# Microcontroller.net
KiCad netlist of a schematic drawn in Altium Designer
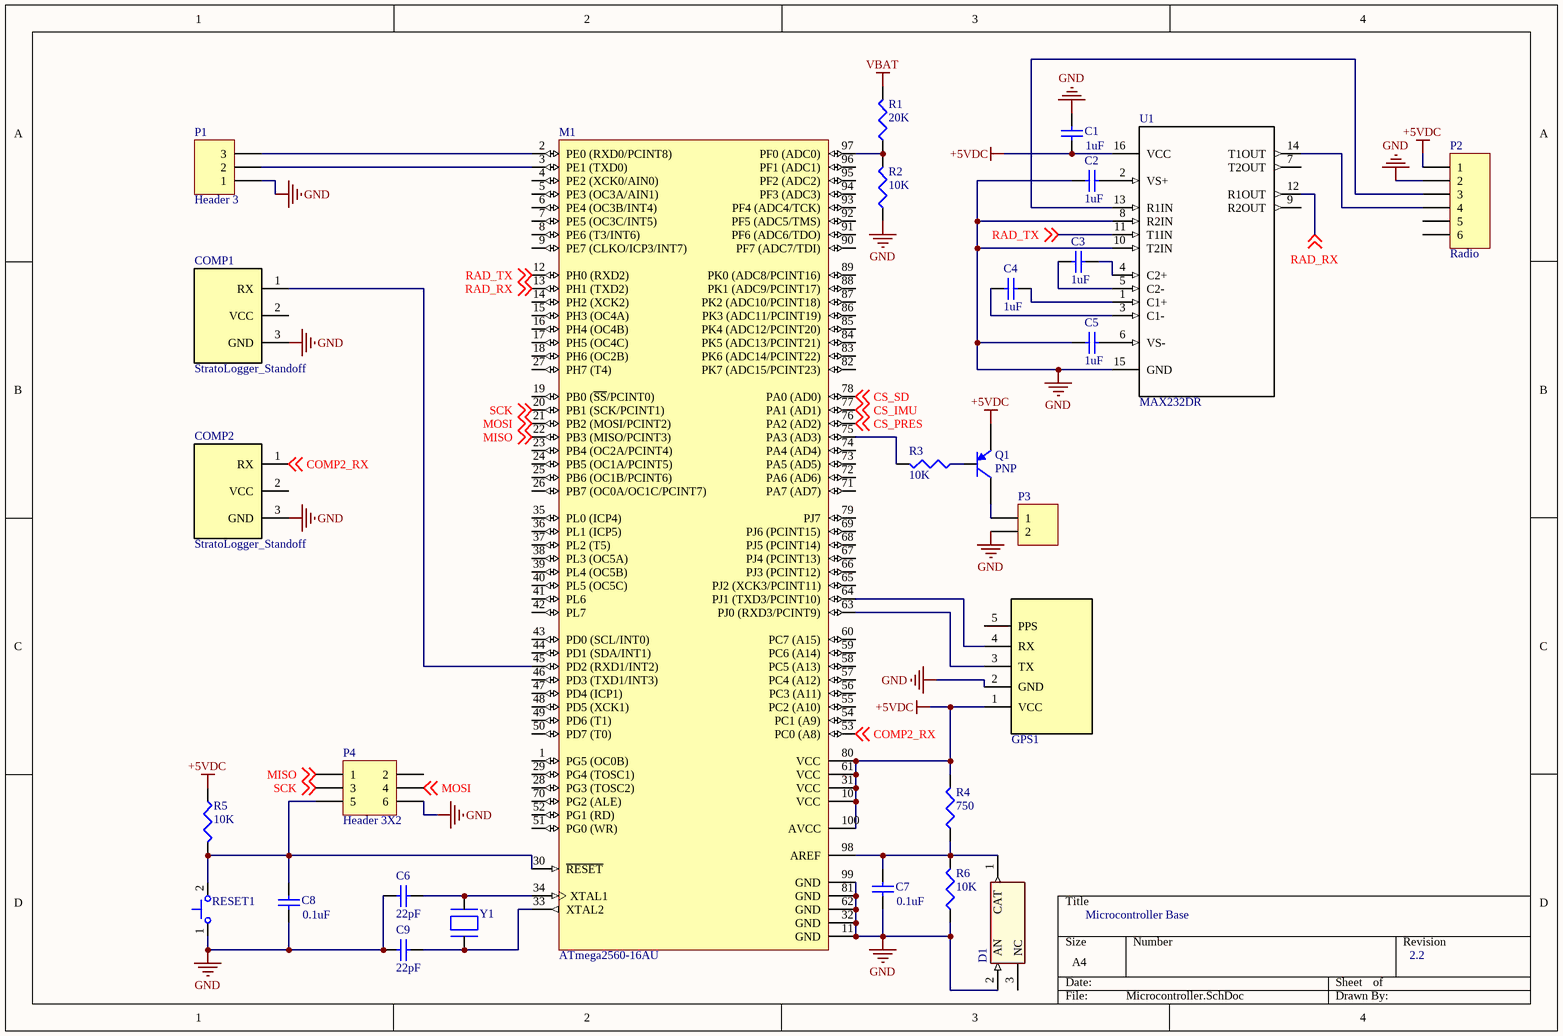
[diagram p0: Microcontroller.SchDoc]

(export (version "E")
  (design (tool "Eeschema 10.0.6"))
  (components
    (comp (ref "C1")
      (value "1uF")
      (footprint "1608[0603]")
      (description "Capacitor (Semiconductor SIM Model)")
      (fields (field (name "Comment") "Cap Semi") (field (name "PUBLISHER") "Altium Limited"))
      (libsource (lib "Miscellaneous Devices") (part "Cap Semi"))
    )
    (comp (ref "C2")
      (value "1uF")
      (footprint "1608[0603]")
      (description "Capacitor (Semiconductor SIM Model)")
      (fields (field (name "Comment") "Cap Semi") (field (name "PUBLISHER") "Altium Limited"))
      (libsource (lib "Miscellaneous Devices") (part "Cap Semi"))
    )
    (comp (ref "C3")
      (value "1uF")
      (footprint "1608[0603]")
      (description "Capacitor (Semiconductor SIM Model)")
      (fields (field (name "Comment") "Cap Semi") (field (name "PUBLISHER") "Altium Limited"))
      (libsource (lib "Miscellaneous Devices") (part "Cap Semi"))
    )
    (comp (ref "C4")
      (value "1uF")
      (footprint "1608[0603]")
      (description "Capacitor (Semiconductor SIM Model)")
      (fields (field (name "Comment") "Cap Semi") (field (name "PUBLISHER") "Altium Limited"))
      (libsource (lib "Miscellaneous Devices") (part "Cap Semi"))
    )
    (comp (ref "C5")
      (value "1uF")
      (footprint "1608[0603]")
      (description "Capacitor (Semiconductor SIM Model)")
      (fields (field (name "Comment") "Cap Semi") (field (name "PUBLISHER") "Altium Limited"))
      (libsource (lib "Miscellaneous Devices") (part "Cap Semi"))
    )
    (comp (ref "C6")
      (value "22pF")
      (footprint "1608[0603]")
      (description "Capacitor (Semiconductor SIM Model)")
      (fields (field (name "Comment") "Cap Semi") (field (name "PUBLISHER") "Altium Limited"))
      (libsource (lib "Miscellaneous Devices") (part "Cap Semi"))
    )
    (comp (ref "C7")
      (value "0.1uF")
      (footprint "1608[0603]")
      (description "Capacitor (Semiconductor SIM Model)")
      (fields (field (name "Comment") "Cap Semi") (field (name "PUBLISHER") "Altium Limited"))
      (libsource (lib "Miscellaneous Devices") (part "Cap Semi"))
    )
    (comp (ref "C8")
      (value "0.1uF")
      (footprint "1608[0603]")
      (description "Capacitor (Semiconductor SIM Model)")
      (fields (field (name "Comment") "Cap Semi") (field (name "PUBLISHER") "Altium Limited"))
      (libsource (lib "Miscellaneous Devices") (part "Cap Semi"))
    )
    (comp (ref "C9")
      (value "22pF")
      (footprint "1608[0603]")
      (description "Capacitor (Semiconductor SIM Model)")
      (fields (field (name "Comment") "Cap Semi") (field (name "PUBLISHER") "Altium Limited"))
      (libsource (lib "Miscellaneous Devices") (part "Cap Semi"))
    )
    (comp (ref "COMP1")
      (value "StratoLogger_Standoff")
      (footprint "StratoLogger_S")
      (libsource (lib "CustomCompLib") (part "StratoLogger_Standoff"))
    )
    (comp (ref "COMP2")
      (value "StratoLogger_Standoff")
      (footprint "StratoLogger_S")
      (libsource (lib "CustomCompLib") (part "StratoLogger_Standoff"))
    )
    (comp (ref "D1")
      (value "LM4040A82IDBZR")
      (footprint "SOT95P237X112-3N")
      (description "Precision Micropower Shunt Voltage Reference, 0.1% accuracy 3-SOT-23 -40 to 85")
      (fields (field (name "MF") "Texas Instruments"))
      (libsource (lib "CustomCompLib") (part "LM4040A82IDBZR"))
    )
    (comp (ref "GPS1")
      (value "Neo 6M GPS")
      (footprint "Neo 6M GPS")
      (libsource (lib "CustomCompLib") (part "Neo 6M GPS"))
    )
    (comp (ref "M1")
      (value "ATmega2560-16AU")
      (footprint "100A_N")
      (fields (field (name "PUBLISHER") "Altium Limited"))
      (libsource (lib "Atmel Microcontroller 8-Bit megaAVR") (part "ATmega2560-16AU"))
    )
    (comp (ref "P1")
      (value "Header 3")
      (footprint "HDR1X3")
      (description "Header, 3-Pin")
      (fields (field (name "PUBLISHER") "Altium Limited"))
      (libsource (lib "Miscellaneous Connectors") (part "Header 3"))
    )
    (comp (ref "P2")
      (value "Radio")
      (footprint "HDR1X6")
      (description "Header, 6-Pin")
      (fields (field (name "PUBLISHER") "Altium Limited"))
      (libsource (lib "Miscellaneous Connectors") (part "Header 6"))
    )
    (comp (ref "P3")
      (value "Header 2")
      (footprint "HDR1X2")
      (description "Header, 2-Pin")
      (fields (field (name "PUBLISHER") "Altium Limited"))
      (libsource (lib "Miscellaneous Connectors") (part "Header 2"))
    )
    (comp (ref "P4")
      (value "Header 3X2")
      (footprint "HDR2X3")
      (description "Header, 3-Pin, Dual row")
      (fields (field (name "PUBLISHER") "Altium Limited"))
      (libsource (lib "Miscellaneous Connectors") (part "Header 3X2"))
    )
    (comp (ref "Q1")
      (value "PNP")
      (footprint "SOT-23B_N")
      (description "PNP Bipolar Transistor")
      (fields (field (name "PUBLISHER") "Altium Limited"))
      (libsource (lib "Miscellaneous Devices") (part "PNP"))
    )
    (comp (ref "R1")
      (value "20K")
      (footprint "J1-0603")
      (description "Resistor")
      (fields (field (name "Comment") "Res3") (field (name "PUBLISHER") "Altium Limited"))
      (libsource (lib "Miscellaneous Devices") (part "Res3"))
    )
    (comp (ref "R2")
      (value "10K")
      (footprint "J1-0603")
      (description "Resistor")
      (fields (field (name "Comment") "Res3") (field (name "PUBLISHER") "Altium Limited"))
      (libsource (lib "Miscellaneous Devices") (part "Res3"))
    )
    (comp (ref "R3")
      (value "10K")
      (footprint "J1-0603")
      (description "Resistor")
      (fields (field (name "Comment") "Res3") (field (name "PUBLISHER") "Altium Limited"))
      (libsource (lib "Miscellaneous Devices") (part "Res3"))
    )
    (comp (ref "R4")
      (value "750")
      (footprint "J1-0603")
      (description "Resistor")
      (fields (field (name "Comment") "Res3") (field (name "PUBLISHER") "Altium Limited"))
      (libsource (lib "Miscellaneous Devices") (part "Res3"))
    )
    (comp (ref "R5")
      (value "10K")
      (footprint "J1-0603")
      (description "Resistor")
      (fields (field (name "Comment") "Res3") (field (name "PUBLISHER") "Altium Limited"))
      (libsource (lib "Miscellaneous Devices") (part "Res3"))
    )
    (comp (ref "R6")
      (value "10K")
      (footprint "J1-0603")
      (description "Resistor")
      (fields (field (name "Comment") "Res3") (field (name "PUBLISHER") "Altium Limited"))
      (libsource (lib "Miscellaneous Devices") (part "Res3"))
    )
    (comp (ref "RESET1")
      (value "KSS221GLFS")
      (footprint "KSS-2G")
      (fields (field (name "PUBLISHER") "Altium Limited"))
      (libsource (lib "CK Switch") (part "KSS221GLFS"))
    )
    (comp (ref "U1")
      (value "MAX232DR")
      (footprint "SOIC127P600X175-16N")
      (description "Single Supply Voltage, RS-232 Transceiver")
      (fields (field (name "MF") "Texas Instruments"))
      (libsource (lib "MAX232DR") (part "MAX232DR"))
    )
    (comp (ref "Y1")
      (value "Crystal SMD")
      (footprint "Crystal SMD")
      (libsource (lib "CustomCompLib") (part "Crystal SMD"))
    )
  )
  (nets
    (net (code "1") (name "+5VDC") (class "Default")
      (node (ref "C1") (pin "1") (pinfunction "1_1") (pintype "passive"))
      (node (ref "GPS1") (pin "1") (pinfunction "VCC_1") (pintype "passive"))
      (node (ref "M1") (pin "10") (pinfunction "VCC_10") (pintype "power_in"))
      (node (ref "M1") (pin "100") (pinfunction "AVCC_100") (pintype "power_in"))
      (node (ref "M1") (pin "31") (pinfunction "VCC_31") (pintype "power_in"))
      (node (ref "M1") (pin "61") (pinfunction "VCC_61") (pintype "power_in"))
      (node (ref "M1") (pin "80") (pinfunction "VCC_80") (pintype "power_in"))
      (node (ref "P2") (pin "1") (pinfunction "1_1") (pintype "passive"))
      (node (ref "Q1") (pin "3") (pinfunction "E_3") (pintype "passive"))
      (node (ref "R4") (pin "2") (pinfunction "2_2") (pintype "passive"))
      (node (ref "R5") (pin "1") (pinfunction "1_1") (pintype "passive"))
      (node (ref "U1") (pin "16") (pinfunction "VCC_16") (pintype "power_in"))
    )
    (net (code "2") (name "COMP2_RX") (class "Default")
      (node (ref "COMP2") (pin "1") (pinfunction "RX_1") (pintype "passive"))
      (node (ref "M1") (pin "53") (pinfunction "PC0_(A8)_53") (pintype "bidirectional"))
    )
    (net (code "3") (name "CS_IMU") (class "Default")
      (node (ref "M1") (pin "77") (pinfunction "PA1_(AD1)_77") (pintype "bidirectional"))
    )
    (net (code "4") (name "CS_PRES") (class "Default")
      (node (ref "M1") (pin "76") (pinfunction "PA2_(AD2)_76") (pintype "bidirectional"))
    )
    (net (code "5") (name "CS_SD") (class "Default")
      (node (ref "M1") (pin "78") (pinfunction "PA0_(AD0)_78") (pintype "bidirectional"))
    )
    (net (code "6") (name "GND") (class "Default")
      (node (ref "C1") (pin "2") (pinfunction "2_2") (pintype "passive"))
      (node (ref "C2") (pin "2") (pinfunction "2_2") (pintype "passive"))
      (node (ref "C5") (pin "2") (pinfunction "2_2") (pintype "passive"))
      (node (ref "C6") (pin "1") (pinfunction "1_1") (pintype "passive"))
      (node (ref "C7") (pin "1") (pinfunction "1_1") (pintype "passive"))
      (node (ref "C8") (pin "1") (pinfunction "1_1") (pintype "passive"))
      (node (ref "C9") (pin "1") (pinfunction "1_1") (pintype "passive"))
      (node (ref "COMP1") (pin "3") (pinfunction "GND_3") (pintype "passive"))
      (node (ref "COMP2") (pin "3") (pinfunction "GND_3") (pintype "passive"))
      (node (ref "D1") (pin "2") (pinfunction "AN_2") (pintype "input"))
      (node (ref "GPS1") (pin "2") (pinfunction "GND_2") (pintype "passive"))
      (node (ref "M1") (pin "11") (pinfunction "GND_11") (pintype "power_in"))
      (node (ref "M1") (pin "32") (pinfunction "GND_32") (pintype "power_in"))
      (node (ref "M1") (pin "62") (pinfunction "GND_62") (pintype "power_in"))
      (node (ref "M1") (pin "81") (pinfunction "GND_81") (pintype "power_in"))
      (node (ref "M1") (pin "99") (pinfunction "GND_99") (pintype "power_in"))
      (node (ref "P1") (pin "1") (pinfunction "1_1") (pintype "passive"))
      (node (ref "P2") (pin "2") (pinfunction "2_2") (pintype "passive"))
      (node (ref "P3") (pin "2") (pinfunction "2_2") (pintype "passive"))
      (node (ref "P4") (pin "6") (pinfunction "6_6") (pintype "passive"))
      (node (ref "R2") (pin "1") (pinfunction "1_1") (pintype "passive"))
      (node (ref "R6") (pin "1") (pinfunction "1_1") (pintype "passive"))
      (node (ref "RESET1") (pin "1") (pinfunction "1_1") (pintype "passive"))
      (node (ref "U1") (pin "10") (pinfunction "T2IN_10") (pintype "input"))
      (node (ref "U1") (pin "15") (pinfunction "GND_15") (pintype "passive"))
      (node (ref "U1") (pin "8") (pinfunction "R2IN_8") (pintype "input"))
    )
    (net (code "7") (name "MISO") (class "Default")
      (node (ref "M1") (pin "22") (pinfunction "PB3_(MISO/PCINT3)_22") (pintype "bidirectional"))
      (node (ref "P4") (pin "1") (pinfunction "1_1") (pintype "passive"))
    )
    (net (code "8") (name "MOSI") (class "Default")
      (node (ref "M1") (pin "21") (pinfunction "PB2_(MOSI/PCINT2)_21") (pintype "bidirectional"))
      (node (ref "P4") (pin "4") (pinfunction "4_4") (pintype "passive"))
    )
    (net (code "9") (name "Net-(COMP1-RX)") (class "Default")
      (node (ref "COMP1") (pin "1") (pinfunction "RX_1") (pintype "passive"))
      (node (ref "M1") (pin "45") (pinfunction "PD2_(RXD1/INT2)_45") (pintype "bidirectional"))
    )
    (net (code "10") (name "Net-(D1-CAT)") (class "Default")
      (node (ref "C7") (pin "2") (pinfunction "2_2") (pintype "passive"))
      (node (ref "D1") (pin "1") (pinfunction "CAT_1") (pintype "output"))
      (node (ref "M1") (pin "98") (pinfunction "AREF_98") (pintype "power_in"))
      (node (ref "R4") (pin "1") (pinfunction "1_1") (pintype "passive"))
      (node (ref "R6") (pin "2") (pinfunction "2_2") (pintype "passive"))
    )
    (net (code "11") (name "Net-(GPS1-RX)") (class "Default")
      (node (ref "GPS1") (pin "4") (pinfunction "RX_4") (pintype "passive"))
      (node (ref "M1") (pin "64") (pinfunction "PJ1_(TXD3/PCINT10)_64") (pintype "bidirectional"))
    )
    (net (code "12") (name "Net-(GPS1-TX)") (class "Default")
      (node (ref "GPS1") (pin "3") (pinfunction "TX_3") (pintype "passive"))
      (node (ref "M1") (pin "63") (pinfunction "PJ0_(RXD3/PCINT9)_63") (pintype "bidirectional"))
    )
    (net (code "13") (name "Net-(M1-PA3_(AD3))") (class "Default")
      (node (ref "M1") (pin "75") (pinfunction "PA3_(AD3)_75") (pintype "bidirectional"))
      (node (ref "R3") (pin "2") (pinfunction "2_2") (pintype "passive"))
    )
    (net (code "14") (name "Net-(M1-PE0_(RXD0{slash}PCINT8))") (class "Default")
      (node (ref "M1") (pin "2") (pinfunction "PE0_(RXD0/PCINT8)_2") (pintype "bidirectional"))
      (node (ref "P1") (pin "3") (pinfunction "3_3") (pintype "passive"))
    )
    (net (code "15") (name "Net-(M1-PE1_(TXD0))") (class "Default")
      (node (ref "M1") (pin "3") (pinfunction "PE1_(TXD0)_3") (pintype "bidirectional"))
      (node (ref "P1") (pin "2") (pinfunction "2_2") (pintype "passive"))
    )
    (net (code "16") (name "Net-(M1-PF0_(ADC0))") (class "Default")
      (node (ref "M1") (pin "97") (pinfunction "PF0_(ADC0)_97") (pintype "bidirectional"))
      (node (ref "R1") (pin "1") (pinfunction "1_1") (pintype "passive"))
      (node (ref "R2") (pin "2") (pinfunction "2_2") (pintype "passive"))
    )
    (net (code "17") (name "Net-(M1-XTAL1)") (class "Default")
      (node (ref "C6") (pin "2") (pinfunction "2_2") (pintype "passive"))
      (node (ref "M1") (pin "34") (pinfunction "XTAL1_34") (pintype "input"))
      (node (ref "Y1") (pin "1") (pinfunction "1_1") (pintype "passive"))
    )
    (net (code "18") (name "Net-(M1-XTAL2)") (class "Default")
      (node (ref "C9") (pin "2") (pinfunction "2_2") (pintype "passive"))
      (node (ref "M1") (pin "33") (pinfunction "XTAL2_33") (pintype "output"))
      (node (ref "Y1") (pin "2") (pinfunction "2_2") (pintype "passive"))
    )
    (net (code "19") (name "Net-(M1-~{RESET})") (class "Default")
      (node (ref "C8") (pin "2") (pinfunction "2_2") (pintype "passive"))
      (node (ref "M1") (pin "30") (pinfunction "~{RESET}_30") (pintype "input"))
      (node (ref "P4") (pin "5") (pinfunction "5_5") (pintype "passive"))
      (node (ref "R5") (pin "2") (pinfunction "2_2") (pintype "passive"))
      (node (ref "RESET1") (pin "2") (pinfunction "2_2") (pintype "passive"))
    )
    (net (code "20") (name "Net-(Q1-B)") (class "Default")
      (node (ref "Q1") (pin "2") (pinfunction "B_2") (pintype "passive"))
      (node (ref "R3") (pin "1") (pinfunction "1_1") (pintype "passive"))
    )
    (net (code "21") (name "Net-(Q1-C)") (class "Default")
      (node (ref "P3") (pin "1") (pinfunction "1_1") (pintype "passive"))
      (node (ref "Q1") (pin "1") (pinfunction "C_1") (pintype "passive"))
    )
    (net (code "22") (name "Net-(U1-C1+)") (class "Default")
      (node (ref "C4") (pin "1") (pinfunction "1_1") (pintype "passive"))
      (node (ref "U1") (pin "1") (pinfunction "C1+_1") (pintype "input"))
    )
    (net (code "23") (name "Net-(U1-C1-)") (class "Default")
      (node (ref "C4") (pin "2") (pinfunction "2_2") (pintype "passive"))
      (node (ref "U1") (pin "3") (pinfunction "C1-_3") (pintype "input"))
    )
    (net (code "24") (name "Net-(U1-C2+)") (class "Default")
      (node (ref "C3") (pin "1") (pinfunction "1_1") (pintype "passive"))
      (node (ref "U1") (pin "4") (pinfunction "C2+_4") (pintype "input"))
    )
    (net (code "25") (name "Net-(U1-C2-)") (class "Default")
      (node (ref "C3") (pin "2") (pinfunction "2_2") (pintype "passive"))
      (node (ref "U1") (pin "5") (pinfunction "C2-_5") (pintype "input"))
    )
    (net (code "26") (name "Net-(U1-R1IN)") (class "Default")
      (node (ref "P2") (pin "3") (pinfunction "3_3") (pintype "passive"))
      (node (ref "U1") (pin "13") (pinfunction "R1IN_13") (pintype "input"))
    )
    (net (code "27") (name "Net-(U1-T1OUT)") (class "Default")
      (node (ref "P2") (pin "4") (pinfunction "4_4") (pintype "passive"))
      (node (ref "U1") (pin "14") (pinfunction "T1OUT_14") (pintype "output"))
    )
    (net (code "28") (name "Net-(U1-VS+)") (class "Default")
      (node (ref "C2") (pin "1") (pinfunction "1_1") (pintype "passive"))
      (node (ref "U1") (pin "2") (pinfunction "VS+_2") (pintype "input"))
    )
    (net (code "29") (name "Net-(U1-VS-)") (class "Default")
      (node (ref "C5") (pin "1") (pinfunction "1_1") (pintype "passive"))
      (node (ref "U1") (pin "6") (pinfunction "VS-_6") (pintype "input"))
    )
    (net (code "30") (name "RAD_RX") (class "Default")
      (node (ref "M1") (pin "13") (pinfunction "PH1_(TXD2)_13") (pintype "bidirectional"))
      (node (ref "U1") (pin "12") (pinfunction "R1OUT_12") (pintype "output"))
    )
    (net (code "31") (name "RAD_TX") (class "Default")
      (node (ref "M1") (pin "12") (pinfunction "PH0_(RXD2)_12") (pintype "bidirectional"))
      (node (ref "U1") (pin "11") (pinfunction "T1IN_11") (pintype "input"))
    )
    (net (code "32") (name "SCK") (class "Default")
      (node (ref "M1") (pin "20") (pinfunction "PB1_(SCK/PCINT1)_20") (pintype "bidirectional"))
      (node (ref "P4") (pin "3") (pinfunction "3_3") (pintype "passive"))
    )
    (net (code "33") (name "VBAT") (class "Default")
      (node (ref "R1") (pin "2") (pinfunction "2_2") (pintype "passive"))
    )
    (net (code "34") (name "unconnected-(COMP1-VCC-Pad2)") (class "Default")
      (node (ref "COMP1") (pin "2") (pinfunction "VCC_2") (pintype "passive"))
    )
    (net (code "35") (name "unconnected-(COMP2-VCC-Pad2)") (class "Default")
      (node (ref "COMP2") (pin "2") (pinfunction "VCC_2") (pintype "passive"))
    )
    (net (code "36") (name "unconnected-(D1-NC-Pad3)") (class "Default")
      (node (ref "D1") (pin "3") (pinfunction "NC_3") (pintype "passive"))
    )
    (net (code "37") (name "unconnected-(GPS1-PPS-Pad5)") (class "Default")
      (node (ref "GPS1") (pin "5") (pinfunction "PPS_5") (pintype "passive"))
    )
    (net (code "38") (name "unconnected-(M1-PA4_(AD4)-Pad74)") (class "Default")
      (node (ref "M1") (pin "74") (pinfunction "PA4_(AD4)_74") (pintype "bidirectional"))
    )
    (net (code "39") (name "unconnected-(M1-PA5_(AD5)-Pad73)") (class "Default")
      (node (ref "M1") (pin "73") (pinfunction "PA5_(AD5)_73") (pintype "bidirectional"))
    )
    (net (code "40") (name "unconnected-(M1-PA6_(AD6)-Pad72)") (class "Default")
      (node (ref "M1") (pin "72") (pinfunction "PA6_(AD6)_72") (pintype "bidirectional"))
    )
    (net (code "41") (name "unconnected-(M1-PA7_(AD7)-Pad71)") (class "Default")
      (node (ref "M1") (pin "71") (pinfunction "PA7_(AD7)_71") (pintype "bidirectional"))
    )
    (net (code "42") (name "unconnected-(M1-PB0_(~{SS}{slash}PCINT0)-Pad19)") (class "Default")
      (node (ref "M1") (pin "19") (pinfunction "PB0_(~{SS}/PCINT0)_19") (pintype "bidirectional"))
    )
    (net (code "43") (name "unconnected-(M1-PB4_(OC2A{slash}PCINT4)-Pad23)") (class "Default")
      (node (ref "M1") (pin "23") (pinfunction "PB4_(OC2A/PCINT4)_23") (pintype "bidirectional"))
    )
    (net (code "44") (name "unconnected-(M1-PB5_(OC1A{slash}PCINT5)-Pad24)") (class "Default")
      (node (ref "M1") (pin "24") (pinfunction "PB5_(OC1A/PCINT5)_24") (pintype "bidirectional"))
    )
    (net (code "45") (name "unconnected-(M1-PB6_(OC1B{slash}PCINT6)-Pad25)") (class "Default")
      (node (ref "M1") (pin "25") (pinfunction "PB6_(OC1B/PCINT6)_25") (pintype "bidirectional"))
    )
    (net (code "46") (name "unconnected-(M1-PB7_(OC0A{slash}OC1C{slash}PCINT7)-Pad26)") (class "Default")
      (node (ref "M1") (pin "26") (pinfunction "PB7_(OC0A/OC1C/PCINT7)_26") (pintype "bidirectional"))
    )
    (net (code "47") (name "unconnected-(M1-PC1_(A9)-Pad54)") (class "Default")
      (node (ref "M1") (pin "54") (pinfunction "PC1_(A9)_54") (pintype "bidirectional"))
    )
    (net (code "48") (name "unconnected-(M1-PC2_(A10)-Pad55)") (class "Default")
      (node (ref "M1") (pin "55") (pinfunction "PC2_(A10)_55") (pintype "bidirectional"))
    )
    (net (code "49") (name "unconnected-(M1-PC3_(A11)-Pad56)") (class "Default")
      (node (ref "M1") (pin "56") (pinfunction "PC3_(A11)_56") (pintype "bidirectional"))
    )
    (net (code "50") (name "unconnected-(M1-PC4_(A12)-Pad57)") (class "Default")
      (node (ref "M1") (pin "57") (pinfunction "PC4_(A12)_57") (pintype "bidirectional"))
    )
    (net (code "51") (name "unconnected-(M1-PC5_(A13)-Pad58)") (class "Default")
      (node (ref "M1") (pin "58") (pinfunction "PC5_(A13)_58") (pintype "bidirectional"))
    )
    (net (code "52") (name "unconnected-(M1-PC6_(A14)-Pad59)") (class "Default")
      (node (ref "M1") (pin "59") (pinfunction "PC6_(A14)_59") (pintype "bidirectional"))
    )
    (net (code "53") (name "unconnected-(M1-PC7_(A15)-Pad60)") (class "Default")
      (node (ref "M1") (pin "60") (pinfunction "PC7_(A15)_60") (pintype "bidirectional"))
    )
    (net (code "54") (name "unconnected-(M1-PD0_(SCL{slash}INT0)-Pad43)") (class "Default")
      (node (ref "M1") (pin "43") (pinfunction "PD0_(SCL/INT0)_43") (pintype "bidirectional"))
    )
    (net (code "55") (name "unconnected-(M1-PD1_(SDA{slash}INT1)-Pad44)") (class "Default")
      (node (ref "M1") (pin "44") (pinfunction "PD1_(SDA/INT1)_44") (pintype "bidirectional"))
    )
    (net (code "56") (name "unconnected-(M1-PD3_(TXD1{slash}INT3)-Pad46)") (class "Default")
      (node (ref "M1") (pin "46") (pinfunction "PD3_(TXD1/INT3)_46") (pintype "bidirectional"))
    )
    (net (code "57") (name "unconnected-(M1-PD4_(ICP1)-Pad47)") (class "Default")
      (node (ref "M1") (pin "47") (pinfunction "PD4_(ICP1)_47") (pintype "bidirectional"))
    )
    (net (code "58") (name "unconnected-(M1-PD5_(XCK1)-Pad48)") (class "Default")
      (node (ref "M1") (pin "48") (pinfunction "PD5_(XCK1)_48") (pintype "bidirectional"))
    )
    (net (code "59") (name "unconnected-(M1-PD6_(T1)-Pad49)") (class "Default")
      (node (ref "M1") (pin "49") (pinfunction "PD6_(T1)_49") (pintype "bidirectional"))
    )
    (net (code "60") (name "unconnected-(M1-PD7_(T0)-Pad50)") (class "Default")
      (node (ref "M1") (pin "50") (pinfunction "PD7_(T0)_50") (pintype "bidirectional"))
    )
    (net (code "61") (name "unconnected-(M1-PE2_(XCK0{slash}AIN0)-Pad4)") (class "Default")
      (node (ref "M1") (pin "4") (pinfunction "PE2_(XCK0/AIN0)_4") (pintype "bidirectional"))
    )
    (net (code "62") (name "unconnected-(M1-PE3_(OC3A{slash}AIN1)-Pad5)") (class "Default")
      (node (ref "M1") (pin "5") (pinfunction "PE3_(OC3A/AIN1)_5") (pintype "bidirectional"))
    )
    (net (code "63") (name "unconnected-(M1-PE4_(OC3B{slash}INT4)-Pad6)") (class "Default")
      (node (ref "M1") (pin "6") (pinfunction "PE4_(OC3B/INT4)_6") (pintype "bidirectional"))
    )
    (net (code "64") (name "unconnected-(M1-PE5_(OC3C{slash}INT5)-Pad7)") (class "Default")
      (node (ref "M1") (pin "7") (pinfunction "PE5_(OC3C/INT5)_7") (pintype "bidirectional"))
    )
    (net (code "65") (name "unconnected-(M1-PE6_(T3{slash}INT6)-Pad8)") (class "Default")
      (node (ref "M1") (pin "8") (pinfunction "PE6_(T3/INT6)_8") (pintype "bidirectional"))
    )
    (net (code "66") (name "unconnected-(M1-PE7_(CLKO{slash}ICP3{slash}INT7)-Pad9)") (class "Default")
      (node (ref "M1") (pin "9") (pinfunction "PE7_(CLKO/ICP3/INT7)_9") (pintype "bidirectional"))
    )
    (net (code "67") (name "unconnected-(M1-PF1_(ADC1)-Pad96)") (class "Default")
      (node (ref "M1") (pin "96") (pinfunction "PF1_(ADC1)_96") (pintype "bidirectional"))
    )
    (net (code "68") (name "unconnected-(M1-PF2_(ADC2)-Pad95)") (class "Default")
      (node (ref "M1") (pin "95") (pinfunction "PF2_(ADC2)_95") (pintype "bidirectional"))
    )
    (net (code "69") (name "unconnected-(M1-PF3_(ADC3)-Pad94)") (class "Default")
      (node (ref "M1") (pin "94") (pinfunction "PF3_(ADC3)_94") (pintype "bidirectional"))
    )
    (net (code "70") (name "unconnected-(M1-PF4_(ADC4{slash}TCK)-Pad93)") (class "Default")
      (node (ref "M1") (pin "93") (pinfunction "PF4_(ADC4/TCK)_93") (pintype "bidirectional"))
    )
    (net (code "71") (name "unconnected-(M1-PF5_(ADC5{slash}TMS)-Pad92)") (class "Default")
      (node (ref "M1") (pin "92") (pinfunction "PF5_(ADC5/TMS)_92") (pintype "bidirectional"))
    )
    (net (code "72") (name "unconnected-(M1-PF6_(ADC6{slash}TDO)-Pad91)") (class "Default")
      (node (ref "M1") (pin "91") (pinfunction "PF6_(ADC6/TDO)_91") (pintype "bidirectional"))
    )
    (net (code "73") (name "unconnected-(M1-PF7_(ADC7{slash}TDI)-Pad90)") (class "Default")
      (node (ref "M1") (pin "90") (pinfunction "PF7_(ADC7/TDI)_90") (pintype "bidirectional"))
    )
    (net (code "74") (name "unconnected-(M1-PG0_(WR)-Pad51)") (class "Default")
      (node (ref "M1") (pin "51") (pinfunction "PG0_(WR)_51") (pintype "bidirectional"))
    )
    (net (code "75") (name "unconnected-(M1-PG1_(RD)-Pad52)") (class "Default")
      (node (ref "M1") (pin "52") (pinfunction "PG1_(RD)_52") (pintype "bidirectional"))
    )
    (net (code "76") (name "unconnected-(M1-PG2_(ALE)-Pad70)") (class "Default")
      (node (ref "M1") (pin "70") (pinfunction "PG2_(ALE)_70") (pintype "bidirectional"))
    )
    (net (code "77") (name "unconnected-(M1-PG3_(TOSC2)-Pad28)") (class "Default")
      (node (ref "M1") (pin "28") (pinfunction "PG3_(TOSC2)_28") (pintype "bidirectional"))
    )
    (net (code "78") (name "unconnected-(M1-PG4_(TOSC1)-Pad29)") (class "Default")
      (node (ref "M1") (pin "29") (pinfunction "PG4_(TOSC1)_29") (pintype "bidirectional"))
    )
    (net (code "79") (name "unconnected-(M1-PG5_(OC0B)-Pad1)") (class "Default")
      (node (ref "M1") (pin "1") (pinfunction "PG5_(OC0B)_1") (pintype "bidirectional"))
    )
    (net (code "80") (name "unconnected-(M1-PH2_(XCK2)-Pad14)") (class "Default")
      (node (ref "M1") (pin "14") (pinfunction "PH2_(XCK2)_14") (pintype "bidirectional"))
    )
    (net (code "81") (name "unconnected-(M1-PH3_(OC4A)-Pad15)") (class "Default")
      (node (ref "M1") (pin "15") (pinfunction "PH3_(OC4A)_15") (pintype "bidirectional"))
    )
    (net (code "82") (name "unconnected-(M1-PH4_(OC4B)-Pad16)") (class "Default")
      (node (ref "M1") (pin "16") (pinfunction "PH4_(OC4B)_16") (pintype "bidirectional"))
    )
    (net (code "83") (name "unconnected-(M1-PH5_(OC4C)-Pad17)") (class "Default")
      (node (ref "M1") (pin "17") (pinfunction "PH5_(OC4C)_17") (pintype "bidirectional"))
    )
    (net (code "84") (name "unconnected-(M1-PH6_(OC2B)-Pad18)") (class "Default")
      (node (ref "M1") (pin "18") (pinfunction "PH6_(OC2B)_18") (pintype "bidirectional"))
    )
    (net (code "85") (name "unconnected-(M1-PH7_(T4)-Pad27)") (class "Default")
      (node (ref "M1") (pin "27") (pinfunction "PH7_(T4)_27") (pintype "bidirectional"))
    )
    (net (code "86") (name "unconnected-(M1-PJ2_(XCK3{slash}PCINT11)-Pad65)") (class "Default")
      (node (ref "M1") (pin "65") (pinfunction "PJ2_(XCK3/PCINT11)_65") (pintype "bidirectional"))
    )
    (net (code "87") (name "unconnected-(M1-PJ3_(PCINT12)-Pad66)") (class "Default")
      (node (ref "M1") (pin "66") (pinfunction "PJ3_(PCINT12)_66") (pintype "bidirectional"))
    )
    (net (code "88") (name "unconnected-(M1-PJ4_(PCINT13)-Pad67)") (class "Default")
      (node (ref "M1") (pin "67") (pinfunction "PJ4_(PCINT13)_67") (pintype "bidirectional"))
    )
    (net (code "89") (name "unconnected-(M1-PJ5_(PCINT14)-Pad68)") (class "Default")
      (node (ref "M1") (pin "68") (pinfunction "PJ5_(PCINT14)_68") (pintype "bidirectional"))
    )
    (net (code "90") (name "unconnected-(M1-PJ6_(PCINT15)-Pad69)") (class "Default")
      (node (ref "M1") (pin "69") (pinfunction "PJ6_(PCINT15)_69") (pintype "bidirectional"))
    )
    (net (code "91") (name "unconnected-(M1-PJ7-Pad79)") (class "Default")
      (node (ref "M1") (pin "79") (pinfunction "PJ7_79") (pintype "bidirectional"))
    )
    (net (code "92") (name "unconnected-(M1-PK0_(ADC8{slash}PCINT16)-Pad89)") (class "Default")
      (node (ref "M1") (pin "89") (pinfunction "PK0_(ADC8/PCINT16)_89") (pintype "bidirectional"))
    )
    (net (code "93") (name "unconnected-(M1-PK1_(ADC9{slash}PCINT17)-Pad88)") (class "Default")
      (node (ref "M1") (pin "88") (pinfunction "PK1_(ADC9/PCINT17)_88") (pintype "bidirectional"))
    )
    (net (code "94") (name "unconnected-(M1-PK2_(ADC10{slash}PCINT18)-Pad87)") (class "Default")
      (node (ref "M1") (pin "87") (pinfunction "PK2_(ADC10/PCINT18)_87") (pintype "bidirectional"))
    )
    (net (code "95") (name "unconnected-(M1-PK3_(ADC11{slash}PCINT19)-Pad86)") (class "Default")
      (node (ref "M1") (pin "86") (pinfunction "PK3_(ADC11/PCINT19)_86") (pintype "bidirectional"))
    )
    (net (code "96") (name "unconnected-(M1-PK4_(ADC12{slash}PCINT20)-Pad85)") (class "Default")
      (node (ref "M1") (pin "85") (pinfunction "PK4_(ADC12/PCINT20)_85") (pintype "bidirectional"))
    )
    (net (code "97") (name "unconnected-(M1-PK5_(ADC13{slash}PCINT21)-Pad84)") (class "Default")
      (node (ref "M1") (pin "84") (pinfunction "PK5_(ADC13/PCINT21)_84") (pintype "bidirectional"))
    )
    (net (code "98") (name "unconnected-(M1-PK6_(ADC14{slash}PCINT22)-Pad83)") (class "Default")
      (node (ref "M1") (pin "83") (pinfunction "PK6_(ADC14/PCINT22)_83") (pintype "bidirectional"))
    )
    (net (code "99") (name "unconnected-(M1-PK7_(ADC15{slash}PCINT23)-Pad82)") (class "Default")
      (node (ref "M1") (pin "82") (pinfunction "PK7_(ADC15/PCINT23)_82") (pintype "bidirectional"))
    )
    (net (code "100") (name "unconnected-(M1-PL0_(ICP4)-Pad35)") (class "Default")
      (node (ref "M1") (pin "35") (pinfunction "PL0_(ICP4)_35") (pintype "bidirectional"))
    )
    (net (code "101") (name "unconnected-(M1-PL1_(ICP5)-Pad36)") (class "Default")
      (node (ref "M1") (pin "36") (pinfunction "PL1_(ICP5)_36") (pintype "bidirectional"))
    )
    (net (code "102") (name "unconnected-(M1-PL2_(T5)-Pad37)") (class "Default")
      (node (ref "M1") (pin "37") (pinfunction "PL2_(T5)_37") (pintype "bidirectional"))
    )
    (net (code "103") (name "unconnected-(M1-PL3_(OC5A)-Pad38)") (class "Default")
      (node (ref "M1") (pin "38") (pinfunction "PL3_(OC5A)_38") (pintype "bidirectional"))
    )
    (net (code "104") (name "unconnected-(M1-PL4_(OC5B)-Pad39)") (class "Default")
      (node (ref "M1") (pin "39") (pinfunction "PL4_(OC5B)_39") (pintype "bidirectional"))
    )
    (net (code "105") (name "unconnected-(M1-PL5_(OC5C)-Pad40)") (class "Default")
      (node (ref "M1") (pin "40") (pinfunction "PL5_(OC5C)_40") (pintype "bidirectional"))
    )
    (net (code "106") (name "unconnected-(M1-PL6-Pad41)") (class "Default")
      (node (ref "M1") (pin "41") (pinfunction "PL6_41") (pintype "bidirectional"))
    )
    (net (code "107") (name "unconnected-(M1-PL7-Pad42)") (class "Default")
      (node (ref "M1") (pin "42") (pinfunction "PL7_42") (pintype "bidirectional"))
    )
    (net (code "108") (name "unconnected-(P2-Pad5)") (class "Default")
      (node (ref "P2") (pin "5") (pinfunction "5_5") (pintype "passive"))
    )
    (net (code "109") (name "unconnected-(P2-Pad6)") (class "Default")
      (node (ref "P2") (pin "6") (pinfunction "6_6") (pintype "passive"))
    )
    (net (code "110") (name "unconnected-(P4-Pad2)") (class "Default")
      (node (ref "P4") (pin "2") (pinfunction "2_2") (pintype "passive"))
    )
    (net (code "111") (name "unconnected-(U1-R2OUT-Pad9)") (class "Default")
      (node (ref "U1") (pin "9") (pinfunction "R2OUT_9") (pintype "output"))
    )
    (net (code "112") (name "unconnected-(U1-T2OUT-Pad7)") (class "Default")
      (node (ref "U1") (pin "7") (pinfunction "T2OUT_7") (pintype "output"))
    )
  )
)
